# MS5611.net
KiCad netlist of a schematic drawn in Altium Designer
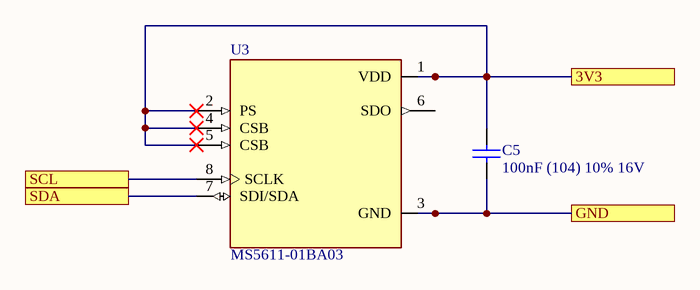
[diagram p0: MS5611.SchDoc]

(export (version "E")
  (design (tool "Eeschema 10.0.6"))
  (components
    (comp (ref "C5")
      (value "100nF (104) 10% 16V")
      (footprint "0402_C")
      (description "贴片电容")
      (libsource (lib "Miscellaneous Devices LC") (part "0402 100nF (104) 10% 16V"))
    )
    (comp (ref "U3")
      (value "MS5611-01BA03")
      (footprint "SON125P500X300X100-8N")
      (description "Pressure Sensor 0.15PSI ~ 17.4PSI _1kPa ~ 120kPa_ Absolute 24 b 8-SMD")
      (fields (field (name "MF") "TE Connectivity"))
      (libsource (lib "MS5611-01BA03") (part "MS5611-01BA03"))
    )
  )
  (nets
    (net (code "1") (name "/3V3") (class "Default")
      (node (ref "C5") (pin "2") (pinfunction "2_2") (pintype "passive"))
      (node (ref "U3") (pin "1") (pinfunction "VDD_1") (pintype "power_in"))
      (node (ref "U3") (pin "2") (pinfunction "PS_2") (pintype "input"))
      (node (ref "U3") (pin "4") (pinfunction "CSB_4") (pintype "input"))
      (node (ref "U3") (pin "5") (pinfunction "CSB_5") (pintype "input"))
    )
    (net (code "2") (name "/GND") (class "Default")
      (node (ref "C5") (pin "1") (pinfunction "1_1") (pintype "passive"))
      (node (ref "U3") (pin "3") (pinfunction "GND_3") (pintype "power_in"))
    )
    (net (code "3") (name "/SCL") (class "Default")
      (node (ref "U3") (pin "8") (pinfunction "SCLK_8") (pintype "input"))
    )
    (net (code "4") (name "/SDA") (class "Default")
      (node (ref "U3") (pin "7") (pinfunction "SDI/SDA_7") (pintype "bidirectional"))
    )
    (net (code "5") (name "unconnected-(U3-SDO-Pad6)") (class "Default")
      (node (ref "U3") (pin "6") (pinfunction "SDO_6") (pintype "output"))
    )
  )
)
